# main.net
KiCad netlist of a schematic drawn in EAGLE
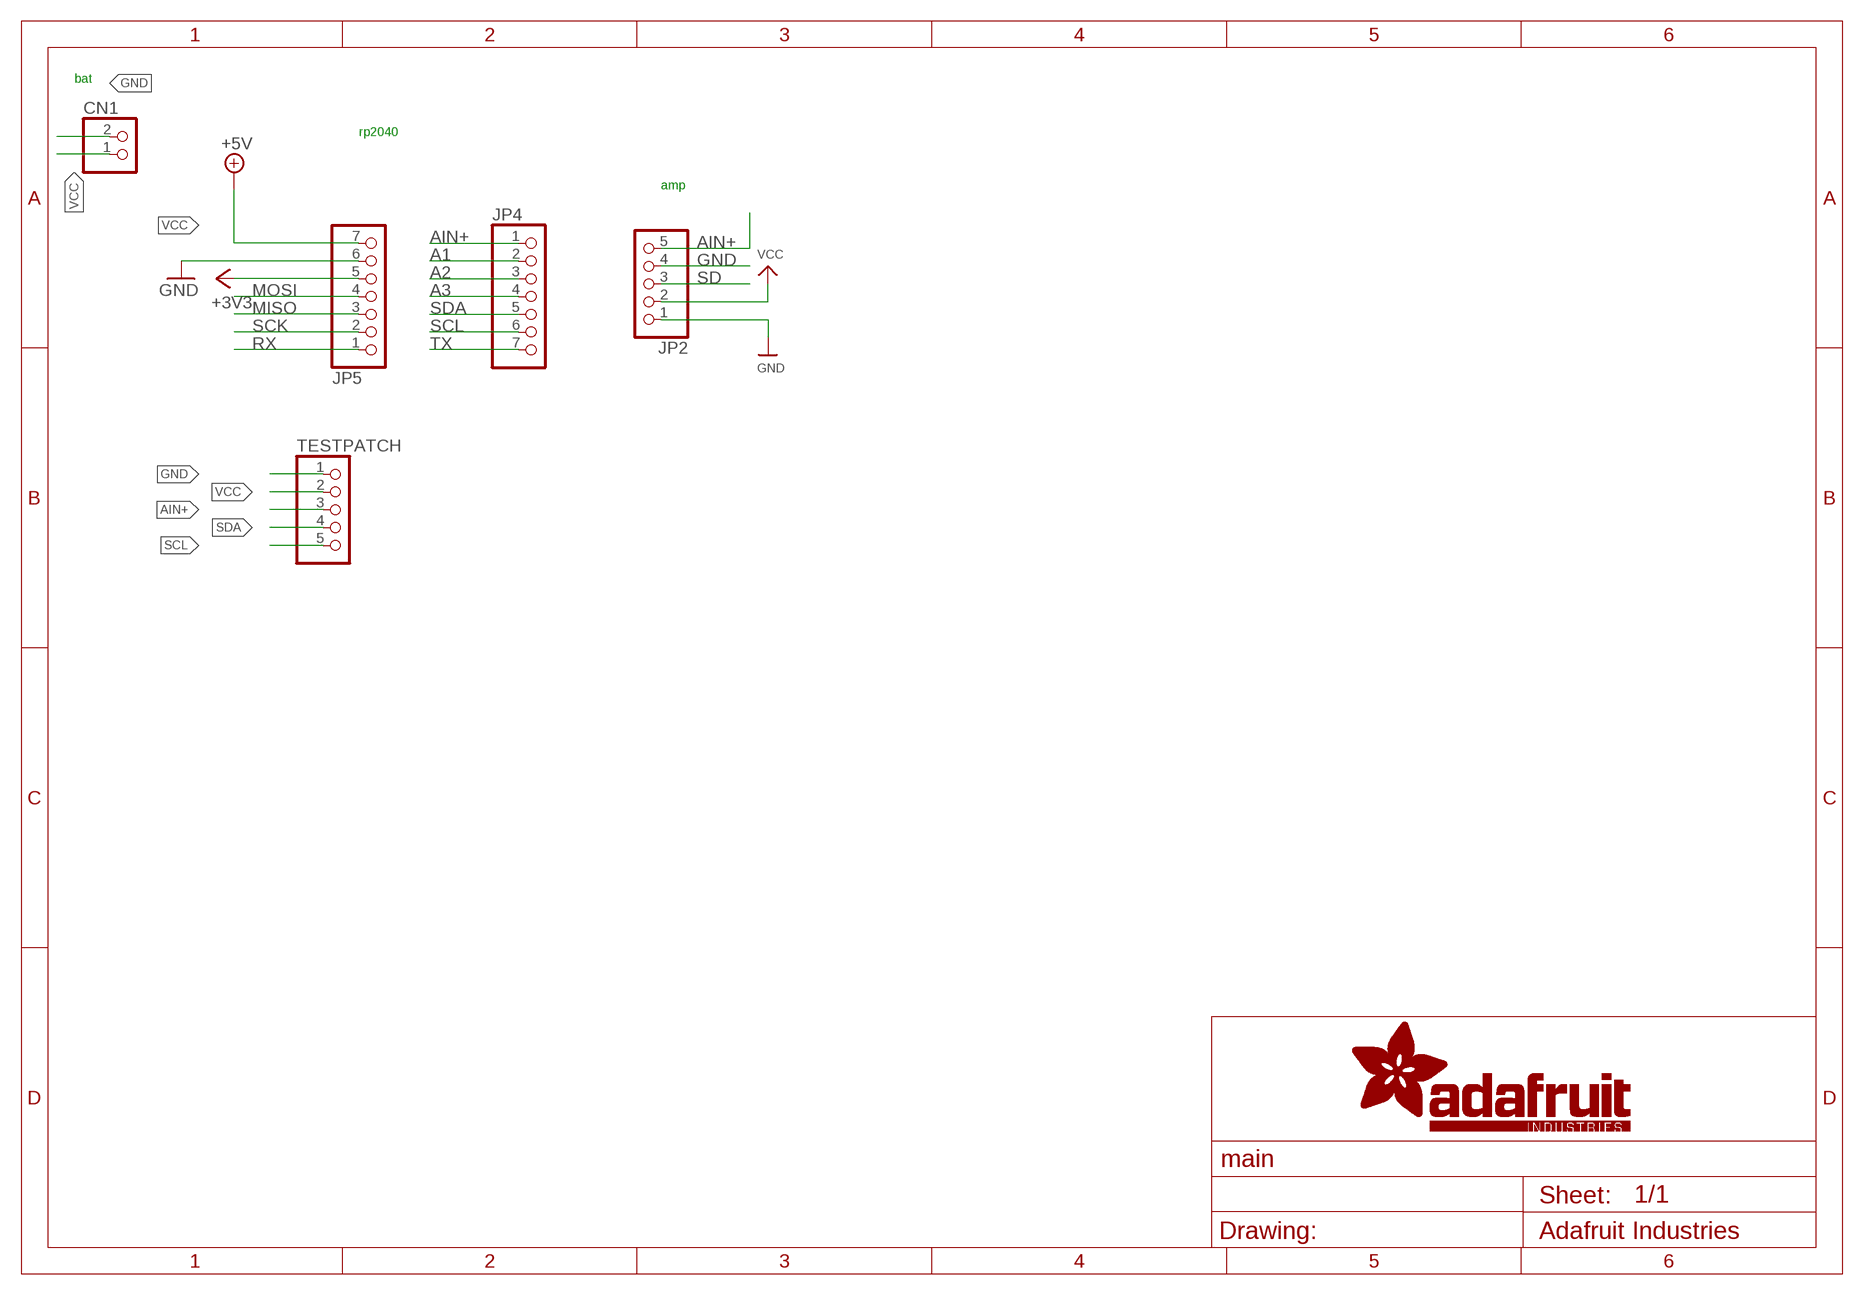
[diagram p0: schematic, sheet 1]

(export (version "E")
  (design (tool "Eeschema 10.0.6"))
  (components
    (comp (ref "CN1")
      (value "JST_2PIN-THM")
      (footprint "eagle-import:JST-PH-2-THM")
      (libsource (lib "eagle-import") (part "JST_2PIN-THM"))
    )
    (comp (ref "JP2")
      (value "HEADER-1X570MIL")
      (footprint "eagle-import:1X05_ROUND_70")
      (libsource (lib "eagle-import") (part "HEADER-1X570MIL"))
    )
    (comp (ref "JP4")
      (value "HEADER-1X7")
      (footprint "eagle-import:1X07_OVAL")
      (libsource (lib "eagle-import") (part "HEADER-1X7"))
    )
    (comp (ref "JP5")
      (value "HEADER-1X7")
      (footprint "eagle-import:1X07_OVAL")
      (libsource (lib "eagle-import") (part "HEADER-1X7"))
    )
    (comp (ref "TESTPATCH")
      (value "PINHD-1X5")
      (footprint "eagle-import:1X05")
      (libsource (lib "eagle-import") (part "PINHD-1X5"))
    )
  )
  (nets
    (net (code "1") (name "+3V3") (class "Default")
      (node (ref "JP5") (pin "5") (pinfunction "5_5") (pintype "passive"))
    )
    (net (code "2") (name "/A1") (class "Default")
      (node (ref "JP4") (pin "2") (pinfunction "2_2") (pintype "passive"))
    )
    (net (code "3") (name "/A2") (class "Default")
      (node (ref "JP4") (pin "3") (pinfunction "3_3") (pintype "passive"))
    )
    (net (code "4") (name "/A3") (class "Default")
      (node (ref "JP4") (pin "4") (pinfunction "4_4") (pintype "passive"))
    )
    (net (code "5") (name "/MISO") (class "Default")
      (node (ref "JP5") (pin "3") (pinfunction "3_3") (pintype "passive"))
    )
    (net (code "6") (name "/MOSI") (class "Default")
      (node (ref "JP5") (pin "4") (pinfunction "4_4") (pintype "passive"))
    )
    (net (code "7") (name "/RX") (class "Default")
      (node (ref "JP5") (pin "1") (pinfunction "1_1") (pintype "passive"))
    )
    (net (code "8") (name "/SCK") (class "Default")
      (node (ref "JP5") (pin "2") (pinfunction "2_2") (pintype "passive"))
    )
    (net (code "9") (name "/SD") (class "Default")
      (node (ref "JP2") (pin "3") (pinfunction "3_3") (pintype "passive"))
    )
    (net (code "10") (name "/TX") (class "Default")
      (node (ref "JP4") (pin "7") (pinfunction "7_7") (pintype "passive"))
    )
    (net (code "11") (name "AIN+") (class "Default")
      (node (ref "JP2") (pin "5") (pinfunction "5_5") (pintype "passive"))
      (node (ref "JP4") (pin "1") (pinfunction "1_1") (pintype "passive"))
      (node (ref "TESTPATCH") (pin "3") (pinfunction "3_3") (pintype "passive"))
    )
    (net (code "12") (name "GND") (class "Default")
      (node (ref "CN1") (pin "2") (pinfunction "1_2") (pintype "passive"))
      (node (ref "JP2") (pin "1") (pinfunction "1_1") (pintype "passive"))
      (node (ref "JP2") (pin "4") (pinfunction "4_4") (pintype "passive"))
      (node (ref "JP5") (pin "6") (pinfunction "6_6") (pintype "passive"))
      (node (ref "TESTPATCH") (pin "1") (pinfunction "1_1") (pintype "passive"))
    )
    (net (code "13") (name "SCL") (class "Default")
      (node (ref "JP4") (pin "6") (pinfunction "6_6") (pintype "passive"))
      (node (ref "TESTPATCH") (pin "5") (pinfunction "5_5") (pintype "passive"))
    )
    (net (code "14") (name "SDA") (class "Default")
      (node (ref "JP4") (pin "5") (pinfunction "5_5") (pintype "passive"))
      (node (ref "TESTPATCH") (pin "4") (pinfunction "4_4") (pintype "passive"))
    )
    (net (code "15") (name "VCC") (class "Default")
      (node (ref "CN1") (pin "1") (pinfunction "2_1") (pintype "passive"))
      (node (ref "JP2") (pin "2") (pinfunction "2_2") (pintype "passive"))
      (node (ref "JP5") (pin "7") (pinfunction "7_7") (pintype "passive"))
      (node (ref "TESTPATCH") (pin "2") (pinfunction "2_2") (pintype "passive"))
    )
  )
)
